# USB-HOST.net
KiCad netlist of a schematic drawn in Altium Designer
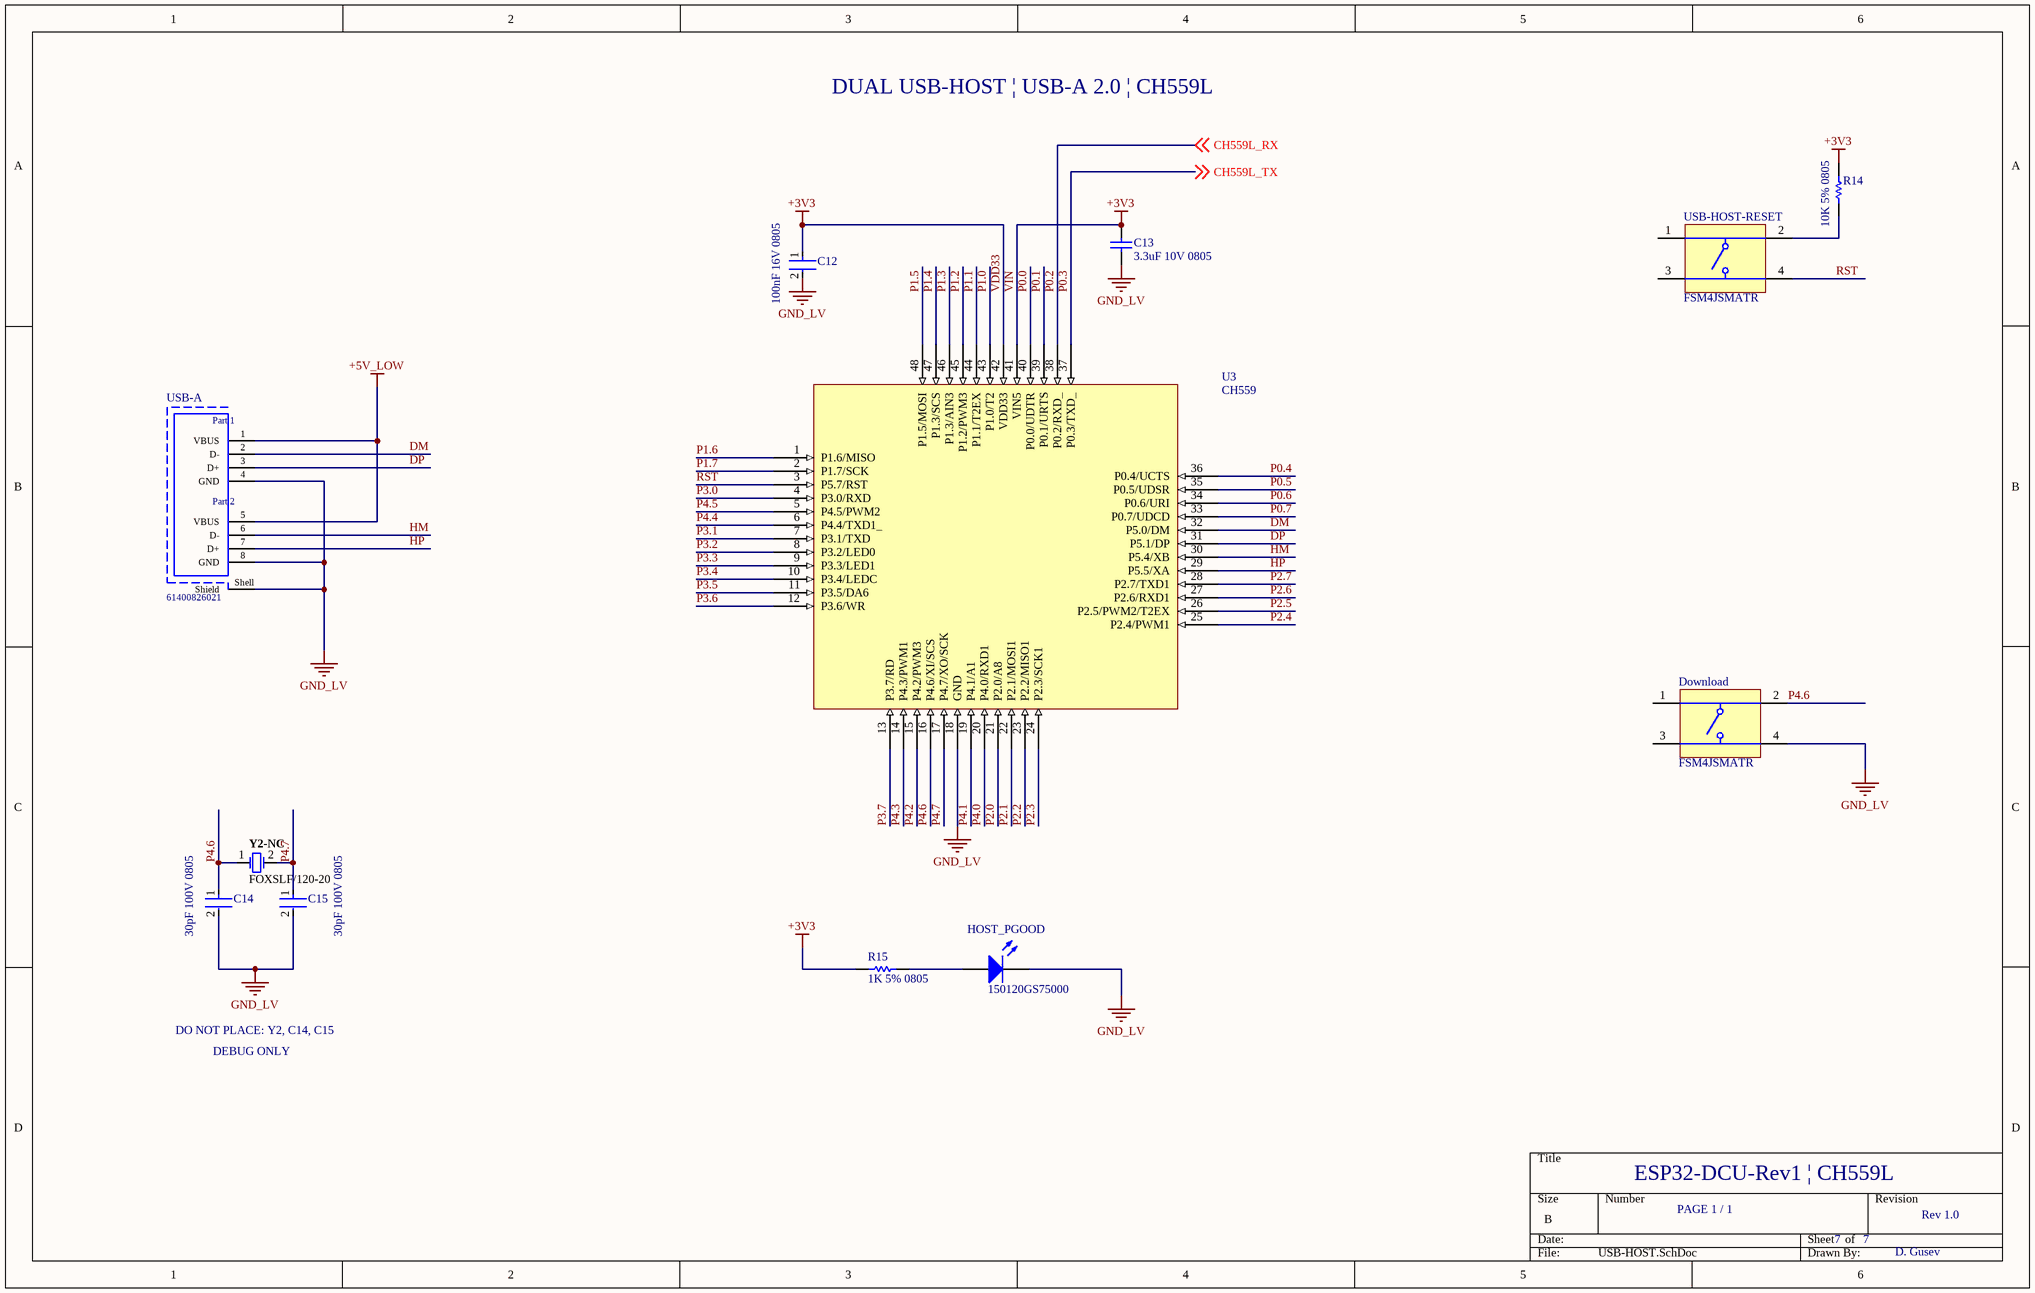
[diagram p0: USB-HOST.SchDoc]

(export (version "E")
  (design (tool "Eeschema 10.0.6"))
  (components
    (comp (ref "C12")
      (value "100nF 16V 0805")
      (footprint "FP-C0805C-DN-MFG")
      (description "CAP CER 0.1UF 50V X7R 0805")
      (fields
        (field (name "MANUFACTURER PART NUMBER") "C0805C104K5RACTU")
        (field (name "MANUFACTURER") "KEMET")
      )
      (libsource (lib "Altium Content Vault") (part "b4654b650e69147ec39a6b967a45e02"))
    )
    (comp (ref "C13")
      (value "3.3uF 10V 0805")
      (footprint "CAPC2013X140X50LL20T25")
      (fields
        (field (name "PART NUMBER") "0805ZD335KAT2A")
        (field (name "MANUFACTURER") "AVX Interconnect / Elco")
      )
      (libsource (lib "Altium Content Vault") (part "CAP"))
    )
    (comp (ref "C14")
      (value "30pF 100V 0805")
      (footprint "FP-C0805C-DN-MFG")
      (description "CAP CER 22PF 100V 5% NP0 0805")
      (fields
        (field (name "OCTOPART") "https://octopart.com/c0805c220j1gactu-kemet-3791395")
        (field (name "TOLERANCE") "0.05")
      )
      (libsource (lib "Altium Content Vault") (part "b4654b650e69147ec39a6b967a45e02"))
    )
    (comp (ref "C15")
      (value "30pF 100V 0805")
      (footprint "FP-C0805C-DN-MFG")
      (description "CAP CER 22PF 100V 5% NP0 0805")
      (fields
        (field (name "OCTOPART") "https://octopart.com/c0805c220j1gactu-kemet-3791395")
        (field (name "TOLERANCE") "0.05")
      )
      (libsource (lib "Altium Content Vault") (part "b4654b650e69147ec39a6b967a45e02"))
    )
    (comp (ref "Download")
      (value "FSM4JSMATR")
      (footprint "TECO-FSM4JSMATR_V")
      (description "Micro Miniature Push Button Switch FSM JSM, 50 mA, -35 to 85 degC, 4-Pin SMD, RoHS, Tape and Reel")
      (fields (field (name "MANUFACTURER") "TE Connectivity"))
      (libsource (lib "Altium Content Vault") (part "SW-SPST-4_A"))
    )
    (comp (ref "HOST_PGOOD")
      (value "150120GS75000")
      (footprint "1206_A")
      (description "SMD mono-color Chip LED, WL-SMCW, Green")
      (fields (field (name "MANUFACTURER") "Wuerth Elektronik"))
      (libsource (lib "Altium Content Vault") (part "WE-LED_K1A2-2"))
    )
    (comp (ref "R14")
      (value "10K 5% 0805")
      (footprint "RESC2013X60X40ML20T25")
      (fields (field (name "PART NUMBER") "ERA6AEB123V") (field (name "MANUFACTURER") "Panasonic"))
      (libsource (lib "Altium Content Vault") (part "RES"))
    )
    (comp (ref "R15")
      (value "1K 5% 0805")
      (footprint "RESC2013X60X40ML20T25")
      (fields (field (name "PART NUMBER") "ERA6AEB123V") (field (name "MANUFACTURER") "Panasonic"))
      (libsource (lib "Altium Content Vault") (part "RES"))
    )
    (comp (ref "U3")
      (value "CH559")
      (footprint "CH559L")
      (description "DUAL USB-HOST 2.0")
      (libsource (lib "ESP32-DCU-Rev1") (part "CH559"))
    )
    (comp (ref "USB-A")
      (value "61400826021")
      (footprint "61400826021")
      (description "USB 2.0 Type A Receptacle WR-COM, Stacked Horizontal, THT")
      (fields (field (name "MANUFACTURER") "Wurth Elektronik") (field (name "PUBLISHER") "WurthElektronik"))
      (libsource (lib "Altium Content Vault") (part "WE-USB-8-1SHLD"))
    )
    (comp (ref "USB-HOST-RESET")
      (value "FSM4JSMATR")
      (footprint "TECO-FSM4JSMATR_V")
      (description "Micro Miniature Push Button Switch FSM JSM, 50 mA, -35 to 85 degC, 4-Pin SMD, RoHS, Tape and Reel")
      (fields (field (name "MANUFACTURER") "TE Connectivity"))
      (libsource (lib "Altium Content Vault") (part "SW-SPST-4_A"))
    )
    (comp (ref "Y2-NC")
      (value "FOXSLF/120-20")
      (footprint "FOX-FOXSLF-2_V")
      (description "Resistance Weld Thru-Hole Crystal, 12 MHz, +/-30 ppm, -20 to 70 degC, 2-Pin THD, RoHS, Bulk")
      (libsource (lib "Altium Content Vault") (part "XTAL-1-2-2"))
    )
  )
  (nets
    (net (code "1") (name "+3V3") (class "Default")
      (node (ref "C12") (pin "1") (pinfunction "1_1") (pintype "passive"))
      (node (ref "C13") (pin "2") (pinfunction "2_2") (pintype "passive"))
      (node (ref "R14") (pin "2") (pinfunction "2_2") (pintype "passive"))
      (node (ref "R15") (pin "2") (pinfunction "2_2") (pintype "passive"))
      (node (ref "U3") (pin "41") (pinfunction "VIN5_41") (pintype "input"))
      (node (ref "U3") (pin "42") (pinfunction "VDD33_42") (pintype "input"))
    )
    (net (code "2") (name "+5V_LOW") (class "Default")
      (node (ref "USB-A") (pin "1") (pinfunction "VBUS_1") (pintype "passive"))
      (node (ref "USB-A") (pin "5") (pinfunction "VBUS_5") (pintype "passive"))
    )
    (net (code "3") (name "/DM") (class "Default")
      (node (ref "U3") (pin "32") (pinfunction "P5.0/DM_32") (pintype "input"))
      (node (ref "USB-A") (pin "2") (pinfunction "D-_2") (pintype "passive"))
    )
    (net (code "4") (name "/DP") (class "Default")
      (node (ref "U3") (pin "31") (pinfunction "P5.1/DP_31") (pintype "input"))
      (node (ref "USB-A") (pin "3") (pinfunction "D+_3") (pintype "passive"))
    )
    (net (code "5") (name "/HM") (class "Default")
      (node (ref "U3") (pin "30") (pinfunction "P5.4/XB_30") (pintype "input"))
      (node (ref "USB-A") (pin "6") (pinfunction "D-_6") (pintype "passive"))
    )
    (net (code "6") (name "/HP") (class "Default")
      (node (ref "U3") (pin "29") (pinfunction "P5.5/XA_29") (pintype "input"))
      (node (ref "USB-A") (pin "7") (pinfunction "D+_7") (pintype "passive"))
    )
    (net (code "7") (name "/P0.0") (class "Default")
      (node (ref "U3") (pin "40") (pinfunction "P0.0/UDTR_40") (pintype "input"))
    )
    (net (code "8") (name "/P0.1") (class "Default")
      (node (ref "U3") (pin "39") (pinfunction "P0.1/URTS_39") (pintype "input"))
    )
    (net (code "9") (name "/P0.4") (class "Default")
      (node (ref "U3") (pin "36") (pinfunction "P0.4/UCTS_36") (pintype "input"))
    )
    (net (code "10") (name "/P0.5") (class "Default")
      (node (ref "U3") (pin "35") (pinfunction "P0.5/UDSR_35") (pintype "input"))
    )
    (net (code "11") (name "/P0.6") (class "Default")
      (node (ref "U3") (pin "34") (pinfunction "P0.6/URI_34") (pintype "input"))
    )
    (net (code "12") (name "/P0.7") (class "Default")
      (node (ref "U3") (pin "33") (pinfunction "P0.7/UDCD_33") (pintype "input"))
    )
    (net (code "13") (name "/P1.0") (class "Default")
      (node (ref "U3") (pin "43") (pinfunction "P1.0/T2_43") (pintype "input"))
    )
    (net (code "14") (name "/P1.1") (class "Default")
      (node (ref "U3") (pin "44") (pinfunction "P1.1/T2EX_44") (pintype "input"))
    )
    (net (code "15") (name "/P1.2") (class "Default")
      (node (ref "U3") (pin "45") (pinfunction "P1.2/PWM3_45") (pintype "input"))
    )
    (net (code "16") (name "/P1.3") (class "Default")
      (node (ref "U3") (pin "46") (pinfunction "P1.3/AIN3_46") (pintype "input"))
    )
    (net (code "17") (name "/P1.4") (class "Default")
      (node (ref "U3") (pin "47") (pinfunction "P1.3/SCS_47") (pintype "input"))
    )
    (net (code "18") (name "/P1.5") (class "Default")
      (node (ref "U3") (pin "48") (pinfunction "P1.5/MOSI_48") (pintype "input"))
    )
    (net (code "19") (name "/P1.6") (class "Default")
      (node (ref "U3") (pin "1") (pinfunction "P1.6/MISO_1") (pintype "input"))
    )
    (net (code "20") (name "/P1.7") (class "Default")
      (node (ref "U3") (pin "2") (pinfunction "P1.7/SCK_2") (pintype "input"))
    )
    (net (code "21") (name "/P2.0") (class "Default")
      (node (ref "U3") (pin "21") (pinfunction "P2.0/A8_21") (pintype "input"))
    )
    (net (code "22") (name "/P2.1") (class "Default")
      (node (ref "U3") (pin "22") (pinfunction "P2.1/MOSI1_22") (pintype "input"))
    )
    (net (code "23") (name "/P2.2") (class "Default")
      (node (ref "U3") (pin "23") (pinfunction "P2.2/MISO1_23") (pintype "input"))
    )
    (net (code "24") (name "/P2.3") (class "Default")
      (node (ref "U3") (pin "24") (pinfunction "P2.3/SCK1_24") (pintype "input"))
    )
    (net (code "25") (name "/P2.4") (class "Default")
      (node (ref "U3") (pin "25") (pinfunction "P2.4/PWM1_25") (pintype "input"))
    )
    (net (code "26") (name "/P2.5") (class "Default")
      (node (ref "U3") (pin "26") (pinfunction "P2.5/PWM2/T2EX_26") (pintype "input"))
    )
    (net (code "27") (name "/P2.6") (class "Default")
      (node (ref "U3") (pin "27") (pinfunction "P2.6/RXD1_27") (pintype "input"))
    )
    (net (code "28") (name "/P2.7") (class "Default")
      (node (ref "U3") (pin "28") (pinfunction "P2.7/TXD1_28") (pintype "input"))
    )
    (net (code "29") (name "/P3.0") (class "Default")
      (node (ref "U3") (pin "4") (pinfunction "P3.0/RXD_4") (pintype "input"))
    )
    (net (code "30") (name "/P3.1") (class "Default")
      (node (ref "U3") (pin "7") (pinfunction "P3.1/TXD_7") (pintype "input"))
    )
    (net (code "31") (name "/P3.2") (class "Default")
      (node (ref "U3") (pin "8") (pinfunction "P3.2/LED0_8") (pintype "input"))
    )
    (net (code "32") (name "/P3.3") (class "Default")
      (node (ref "U3") (pin "9") (pinfunction "P3.3/LED1_9") (pintype "input"))
    )
    (net (code "33") (name "/P3.4") (class "Default")
      (node (ref "U3") (pin "10") (pinfunction "P3.4/LEDC_10") (pintype "input"))
    )
    (net (code "34") (name "/P3.5") (class "Default")
      (node (ref "U3") (pin "11") (pinfunction "P3.5/DA6_11") (pintype "input"))
    )
    (net (code "35") (name "/P3.6") (class "Default")
      (node (ref "U3") (pin "12") (pinfunction "P3.6/WR_12") (pintype "input"))
    )
    (net (code "36") (name "/P3.7") (class "Default")
      (node (ref "U3") (pin "13") (pinfunction "P3.7/RD_13") (pintype "input"))
    )
    (net (code "37") (name "/P4.0") (class "Default")
      (node (ref "U3") (pin "20") (pinfunction "P4.0/RXD1_20") (pintype "input"))
    )
    (net (code "38") (name "/P4.1") (class "Default")
      (node (ref "U3") (pin "19") (pinfunction "P4.1/A1_19") (pintype "input"))
    )
    (net (code "39") (name "/P4.2") (class "Default")
      (node (ref "U3") (pin "15") (pinfunction "P4.2/PWM3_15") (pintype "input"))
    )
    (net (code "40") (name "/P4.3") (class "Default")
      (node (ref "U3") (pin "14") (pinfunction "P4.3/PWM1_14") (pintype "input"))
    )
    (net (code "41") (name "/P4.4") (class "Default")
      (node (ref "U3") (pin "6") (pinfunction "P4.4/TXD1__6") (pintype "input"))
    )
    (net (code "42") (name "/P4.5") (class "Default")
      (node (ref "U3") (pin "5") (pinfunction "P4.5/PWM2_5") (pintype "input"))
    )
    (net (code "43") (name "/P4.6") (class "Default")
      (node (ref "C14") (pin "1") (pinfunction "1_1") (pintype "passive"))
      (node (ref "Download") (pin "2") (pinfunction "2_2") (pintype "passive"))
      (node (ref "U3") (pin "16") (pinfunction "P4.6/XI/SCS_16") (pintype "input"))
      (node (ref "Y2-NC") (pin "1") (pinfunction "1_1") (pintype "passive"))
    )
    (net (code "44") (name "/P4.7") (class "Default")
      (node (ref "C15") (pin "1") (pinfunction "1_1") (pintype "passive"))
      (node (ref "U3") (pin "17") (pinfunction "P4.7/XO/SCK_17") (pintype "input"))
      (node (ref "Y2-NC") (pin "2") (pinfunction "2_2") (pintype "passive"))
    )
    (net (code "45") (name "/RST") (class "Default")
      (node (ref "U3") (pin "3") (pinfunction "P5.7/RST_3") (pintype "input"))
      (node (ref "USB-HOST-RESET") (pin "4") (pinfunction "4_4") (pintype "passive"))
    )
    (net (code "46") (name "CH559L_RX") (class "Default")
      (node (ref "U3") (pin "38") (pinfunction "P0.2/RXD__38") (pintype "input"))
    )
    (net (code "47") (name "CH559L_TX") (class "Default")
      (node (ref "U3") (pin "37") (pinfunction "P0.3/TXD__37") (pintype "input"))
    )
    (net (code "48") (name "GND_LV") (class "Default")
      (node (ref "C12") (pin "2") (pinfunction "2_2") (pintype "passive"))
      (node (ref "C13") (pin "1") (pinfunction "1_1") (pintype "passive"))
      (node (ref "C14") (pin "2") (pinfunction "2_2") (pintype "passive"))
      (node (ref "C15") (pin "2") (pinfunction "2_2") (pintype "passive"))
      (node (ref "Download") (pin "4") (pinfunction "4_4") (pintype "passive"))
      (node (ref "HOST_PGOOD") (pin "1") (pinfunction "K_1") (pintype "passive"))
      (node (ref "U3") (pin "18") (pinfunction "GND_18") (pintype "input"))
      (node (ref "USB-A") (pin "4") (pinfunction "GND_4") (pintype "passive"))
      (node (ref "USB-A") (pin "8") (pinfunction "GND_8") (pintype "passive"))
      (node (ref "USB-A") (pin "Shell") (pinfunction "Shield_Shell") (pintype "passive"))
    )
    (net (code "49") (name "Net-(HOST_PGOOD-A)") (class "Default")
      (node (ref "HOST_PGOOD") (pin "2") (pinfunction "A_2") (pintype "passive"))
      (node (ref "R15") (pin "1") (pinfunction "1_1") (pintype "passive"))
    )
    (net (code "50") (name "Net-(R14-Pad1)") (class "Default")
      (node (ref "R14") (pin "1") (pinfunction "1_1") (pintype "passive"))
      (node (ref "USB-HOST-RESET") (pin "2") (pinfunction "2_2") (pintype "passive"))
    )
    (net (code "51") (name "unconnected-(Download-Pad1)") (class "Default")
      (node (ref "Download") (pin "1") (pinfunction "1_1") (pintype "passive"))
    )
    (net (code "52") (name "unconnected-(Download-Pad3)") (class "Default")
      (node (ref "Download") (pin "3") (pinfunction "3_3") (pintype "passive"))
    )
    (net (code "53") (name "unconnected-(USB-HOST-RESET-Pad1)") (class "Default")
      (node (ref "USB-HOST-RESET") (pin "1") (pinfunction "1_1") (pintype "passive"))
    )
    (net (code "54") (name "unconnected-(USB-HOST-RESET-Pad3)") (class "Default")
      (node (ref "USB-HOST-RESET") (pin "3") (pinfunction "3_3") (pintype "passive"))
    )
  )
)
